# Sheet2.net
KiCad netlist of a schematic drawn in Altium Designer
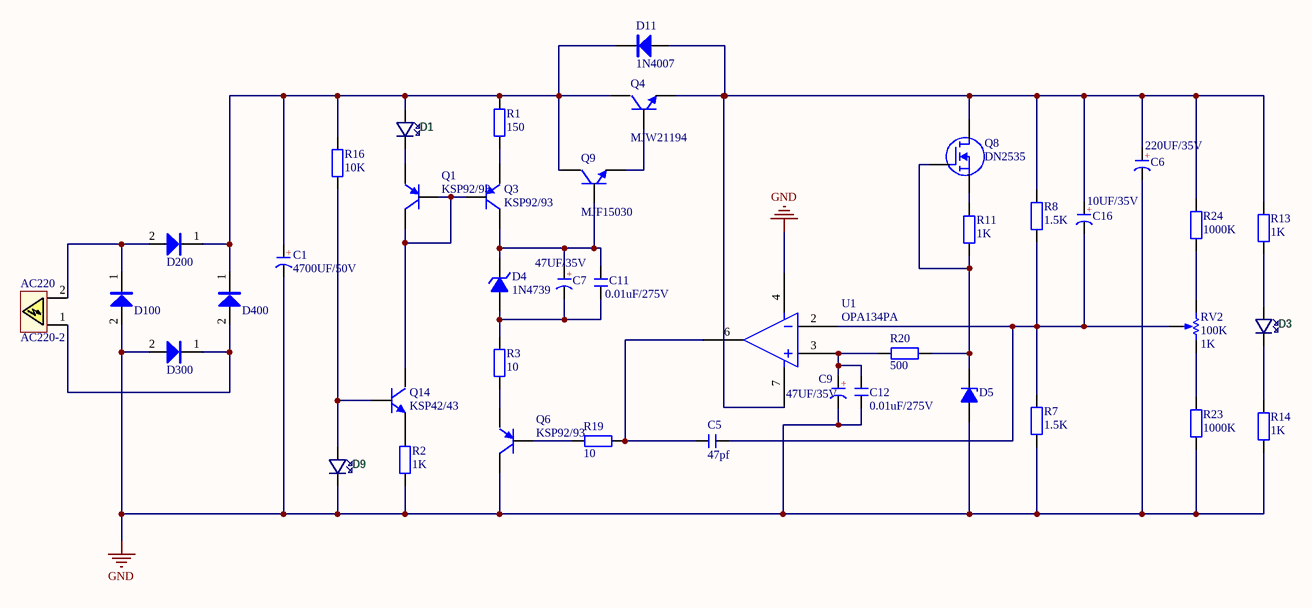
[diagram p0: Sheet2.SchDoc]

(export (version "E")
  (design (tool "Eeschema 10.0.6"))
  (components
    (comp (ref "AC220")
      (value "AC220-2")
      (footprint "HX5.08-2L")
      (libsource (lib "Connectors") (part "AC220-2"))
    )
    (comp (ref "C1")
      (value "4700UF/50V")
      (footprint "CAP 10*22*40")
      (description "直插电解电容")
      (fields (field (name "版权归属") "源创客"))
      (libsource (lib "电阻-电容-电感") (part "C-CAP"))
    )
    (comp (ref "C5")
      (value "47pf")
      (footprint "CC 2.2*5")
      (description "直插瓷片电容")
      (fields (field (name "版权归属") "源创客"))
      (libsource (lib "电阻-电容-电感") (part "C-CC"))
    )
    (comp (ref "C6")
      (value "220UF/35V")
      (footprint "CAP 5.0*10*20")
      (description "直插电解电容")
      (libsource (lib "电阻-电容-电感") (part "C-CAP"))
    )
    (comp (ref "C7")
      (value "47UF/35V")
      (footprint "CAP 5.0*10*20")
      (description "直插电解电容")
      (libsource (lib "电阻-电容-电感") (part "C-CAP"))
    )
    (comp (ref "C9")
      (value "47UF/35V")
      (footprint "CAP 5.0*10*20")
      (description "直插电解电容")
      (fields (field (name "版权归属") "源创客"))
      (libsource (lib "电阻-电容-电感") (part "C-CAP"))
    )
    (comp (ref "C11")
      (value "0.01uF/275V")
      (footprint "CBB 6.3*6.3*5")
      (description "CBB电容")
      (fields (field (name "版权归属") "源创客"))
      (libsource (lib "电阻-电容-电感") (part "C-CBB"))
    )
    (comp (ref "C12")
      (value "0.01uF/275V")
      (footprint "CBB 6.3*6.3*5")
      (description "CBB电容")
      (fields (field (name "版权归属") "源创客"))
      (libsource (lib "电阻-电容-电感") (part "C-CBB"))
    )
    (comp (ref "C16")
      (value "10UF/35V")
      (footprint "CAP 5.0*10*20")
      (description "直插电解电容")
      (libsource (lib "电阻-电容-电感") (part "C-CAP"))
    )
    (comp (ref "D1")
      (value "~")
      (footprint "LED 3MM-R")
      (description "直插式LED")
      (libsource (lib "LED") (part "LED"))
    )
    (comp (ref "D3")
      (value "~")
      (footprint "LED 3MM-R")
      (description "直插式LED")
      (libsource (lib "LED") (part "LED"))
    )
    (comp (ref "D4")
      (value "1N4739")
      (footprint "DO-41")
      (description "9.1V/1W稳压管")
      (libsource (lib "二极管-整流桥") (part "1N4739"))
    )
    (comp (ref "D5")
      (value "LT1021-10-2P")
      (footprint "DIP8-300_MH")
      (description "10V Precision Reference 2 Pin Config")
      (libsource (lib "电压参考") (part "LT1021-10-2P"))
    )
    (comp (ref "D9")
      (value "~")
      (footprint "LED 3MM-R")
      (description "直插式LED")
      (libsource (lib "LED") (part "LED"))
    )
    (comp (ref "D11")
      (value "1N4007")
      (footprint "DO-41")
      (description "整流二极管")
      (libsource (lib "二极管-整流桥") (part "1N4007"))
    )
    (comp (ref "D100")
      (value "VS-HFA08TB60-M3")
      (footprint "TO220AC")
      (description "Ultrafast Soft Recovery Diado 8A 600V")
      (libsource (lib "二极管-整流桥") (part "VS-HFA08TB60-M3"))
    )
    (comp (ref "D200")
      (value "VS-HFA08TB60-M3")
      (footprint "TO220AC")
      (description "Ultrafast Soft Recovery Diado 8A 600V")
      (libsource (lib "二极管-整流桥") (part "VS-HFA08TB60-M3"))
    )
    (comp (ref "D300")
      (value "VS-HFA08TB60-M3")
      (footprint "TO220AC")
      (description "Ultrafast Soft Recovery Diado 8A 600V")
      (libsource (lib "二极管-整流桥") (part "VS-HFA08TB60-M3"))
    )
    (comp (ref "D400")
      (value "VS-HFA08TB60-M3")
      (footprint "TO220AC")
      (description "Ultrafast Soft Recovery Diado 8A 600V")
      (libsource (lib "二极管-整流桥") (part "VS-HFA08TB60-M3"))
    )
    (comp (ref "Q1")
      (value "KSP92/93")
      (footprint "TO92A")
      (description "High Voltage PNP Transistor")
      (libsource (lib "三极管") (part "KSP92/93"))
    )
    (comp (ref "Q3")
      (value "KSP92/93")
      (footprint "TO92A")
      (description "High Voltage PNP Transistor")
      (libsource (lib "三极管") (part "KSP92/93"))
    )
    (comp (ref "Q4")
      (value "MJW21194")
      (footprint "TO247V")
      (description "Power NPN Transistor")
      (libsource (lib "三极管") (part "MJW21194"))
    )
    (comp (ref "Q6")
      (value "KSP92/93")
      (footprint "TO92A")
      (description "High Voltage PNP Transistor")
      (libsource (lib "三极管") (part "KSP92/93"))
    )
    (comp (ref "Q8")
      (value "DN2535")
      (footprint "TO92A")
      (description "N沟道耗尽型DMOS场效应管")
      (libsource (lib "场效应管") (part "DN2535"))
    )
    (comp (ref "Q9")
      (value "MJF15030")
      (footprint "TO220V")
      (description "Power NPN Transistor")
      (libsource (lib "三极管") (part "MJF15030"))
    )
    (comp (ref "Q14")
      (value "KSP42/43")
      (footprint "TO92A")
      (description "High Voltage NPN Transistor")
      (libsource (lib "三极管") (part "KSP42/43"))
    )
    (comp (ref "R1")
      (value "150")
      (footprint "RS 1/4W")
      (description "直插色环电阻")
      (libsource (lib "电阻-电容-电感") (part "R-CRR"))
    )
    (comp (ref "R2")
      (value "1K")
      (footprint "RS 1/4W")
      (description "直插色环电阻")
      (libsource (lib "电阻-电容-电感") (part "R-CRR"))
    )
    (comp (ref "R3")
      (value "10")
      (footprint "RS 1/4W")
      (description "直插色环电阻")
      (libsource (lib "电阻-电容-电感") (part "R-CRR"))
    )
    (comp (ref "R7")
      (value "1.5K")
      (footprint "RS 1/4W")
      (description "直插色环电阻")
      (libsource (lib "电阻-电容-电感") (part "R-CRR"))
    )
    (comp (ref "R8")
      (value "1.5K")
      (footprint "RS 1/4W")
      (description "直插色环电阻")
      (libsource (lib "电阻-电容-电感") (part "R-CRR"))
    )
    (comp (ref "R11")
      (value "1K")
      (footprint "RS 1/4W")
      (description "直插色环电阻")
      (libsource (lib "电阻-电容-电感") (part "R-CRR"))
    )
    (comp (ref "R13")
      (value "1K")
      (footprint "RS 1/4W")
      (description "直插色环电阻")
      (libsource (lib "电阻-电容-电感") (part "R-CRR"))
    )
    (comp (ref "R14")
      (value "1K")
      (footprint "RS 1/4W")
      (description "直插色环电阻")
      (fields (field (name "版权归属") "源创客"))
      (libsource (lib "电阻-电容-电感") (part "R-CRR"))
    )
    (comp (ref "R16")
      (value "10K")
      (footprint "RS 1/4W")
      (description "直插色环电阻")
      (fields (field (name "版权归属") "源创客"))
      (libsource (lib "电阻-电容-电感") (part "R-CRR"))
    )
    (comp (ref "R19")
      (value "10")
      (footprint "RS 1/4W")
      (description "直插色环电阻")
      (libsource (lib "电阻-电容-电感") (part "R-CRR"))
    )
    (comp (ref "R20")
      (value "500")
      (footprint "RS 1/4W")
      (description "直插色环电阻")
      (libsource (lib "电阻-电容-电感") (part "R-CRR"))
    )
    (comp (ref "R23")
      (value "1000K")
      (footprint "RS 1/4W")
      (description "直插色环电阻")
      (libsource (lib "电阻-电容-电感") (part "R-CRR"))
    )
    (comp (ref "R24")
      (value "1000K")
      (footprint "RS 1/4W")
      (description "直插色环电阻")
      (libsource (lib "电阻-电容-电感") (part "R-CRR"))
    )
    (comp (ref "RV2")
      (value "100K")
      (footprint "VR5")
      (description "Potentiometer")
      (fields (field (name "ALTIUM_VALUE") "1K") (field (name "PUBLISHER") "Altium Limited"))
      (libsource (lib "Miscellaneous Devices") (part "RPot"))
    )
    (comp (ref "U1") (value "OPA134PA") (footprint "DIP8-300_MH") (libsource (lib "运放") (part "OPA134PA")))
  )
  (nets
    (net (code "1") (name "GND") (class "Default")
      (node (ref "C1") (pin "2") (pinfunction "K_2") (pintype "passive"))
      (node (ref "C12") (pin "2") (pinfunction "2_2") (pintype "passive"))
      (node (ref "C6") (pin "2") (pinfunction "K_2") (pintype "passive"))
      (node (ref "C9") (pin "2") (pinfunction "K_2") (pintype "passive"))
      (node (ref "D100") (pin "2") (pinfunction "Anode_2") (pintype "passive"))
      (node (ref "D300") (pin "2") (pinfunction "Anode_2") (pintype "passive"))
      (node (ref "D5") (pin "4") (pinfunction "A_4") (pintype "passive"))
      (node (ref "D9") (pin "K") (pintype "passive"))
      (node (ref "Q6") (pin "3") (pinfunction "C_3") (pintype "passive"))
      (node (ref "R14") (pin "1") (pinfunction "1_1") (pintype "passive"))
      (node (ref "R2") (pin "1") (pinfunction "1_1") (pintype "passive"))
      (node (ref "R23") (pin "1") (pinfunction "1_1") (pintype "passive"))
      (node (ref "R7") (pin "1") (pinfunction "1_1") (pintype "passive"))
      (node (ref "U1") (pin "4") (pinfunction "V-_4") (pintype "passive"))
    )
    (net (code "2") (name "Net-(AC220-G)") (class "Default")
      (node (ref "AC220") (pin "2") (pinfunction "G_2") (pintype "passive"))
      (node (ref "D100") (pin "1") (pinfunction "Cathode_1") (pintype "passive"))
      (node (ref "D200") (pin "2") (pinfunction "Anode_2") (pintype "passive"))
    )
    (net (code "3") (name "Net-(AC220-L)") (class "Default")
      (node (ref "AC220") (pin "1") (pinfunction "L_1") (pintype "passive"))
      (node (ref "D300") (pin "1") (pinfunction "Cathode_1") (pintype "passive"))
      (node (ref "D400") (pin "2") (pinfunction "Anode_2") (pintype "passive"))
    )
    (net (code "4") (name "Net-(C1-A)") (class "Default")
      (node (ref "C1") (pin "1") (pinfunction "A_1") (pintype "passive"))
      (node (ref "D1") (pin "A") (pintype "passive"))
      (node (ref "D11") (pin "2") (pinfunction "K_2") (pintype "passive"))
      (node (ref "D200") (pin "1") (pinfunction "Cathode_1") (pintype "passive"))
      (node (ref "D400") (pin "1") (pinfunction "Cathode_1") (pintype "passive"))
      (node (ref "Q4") (pin "2") (pinfunction "C_2") (pintype "passive"))
      (node (ref "Q9") (pin "2") (pinfunction "C_2") (pintype "passive"))
      (node (ref "R1") (pin "2") (pinfunction "2_2") (pintype "passive"))
      (node (ref "R16") (pin "2") (pinfunction "2_2") (pintype "passive"))
    )
    (net (code "5") (name "Net-(C7-A)") (class "Default")
      (node (ref "C11") (pin "1") (pinfunction "1_1") (pintype "passive"))
      (node (ref "C7") (pin "1") (pinfunction "A_1") (pintype "passive"))
      (node (ref "D4") (pin "2") (pinfunction "K_2") (pintype "passive"))
      (node (ref "Q3") (pin "3") (pinfunction "C_3") (pintype "passive"))
      (node (ref "Q9") (pin "1") (pinfunction "B_1") (pintype "passive"))
    )
    (net (code "6") (name "Net-(C7-K)") (class "Default")
      (node (ref "C11") (pin "2") (pinfunction "2_2") (pintype "passive"))
      (node (ref "C7") (pin "2") (pinfunction "K_2") (pintype "passive"))
      (node (ref "D4") (pin "1") (pinfunction "A_1") (pintype "passive"))
      (node (ref "R3") (pin "2") (pinfunction "2_2") (pintype "passive"))
    )
    (net (code "7") (name "Net-(C9-A)") (class "Default")
      (node (ref "C12") (pin "1") (pinfunction "1_1") (pintype "passive"))
      (node (ref "C9") (pin "1") (pinfunction "A_1") (pintype "passive"))
      (node (ref "R20") (pin "2") (pinfunction "2_2") (pintype "passive"))
      (node (ref "U1") (pin "3") (pinfunction "+in_3") (pintype "passive"))
    )
    (net (code "8") (name "Net-(C16-A)") (class "Default")
      (node (ref "C16") (pin "1") (pinfunction "A_1") (pintype "passive"))
      (node (ref "C6") (pin "1") (pinfunction "A_1") (pintype "passive"))
      (node (ref "D11") (pin "1") (pinfunction "A_1") (pintype "passive"))
      (node (ref "Q4") (pin "3") (pinfunction "E_3") (pintype "passive"))
      (node (ref "Q8") (pin "3") (pinfunction "D_3") (pintype "passive"))
      (node (ref "R13") (pin "2") (pinfunction "2_2") (pintype "passive"))
      (node (ref "R24") (pin "2") (pinfunction "2_2") (pintype "passive"))
      (node (ref "R8") (pin "2") (pinfunction "2_2") (pintype "passive"))
      (node (ref "U1") (pin "7") (pinfunction "V+_7") (pintype "passive"))
    )
    (net (code "9") (name "Net-(C16-K)") (class "Default")
      (node (ref "C16") (pin "2") (pinfunction "K_2") (pintype "passive"))
      (node (ref "C5") (pin "2") (pinfunction "2_2") (pintype "passive"))
      (node (ref "R7") (pin "2") (pinfunction "2_2") (pintype "passive"))
      (node (ref "R8") (pin "1") (pinfunction "1_1") (pintype "passive"))
      (node (ref "RV2") (pin "3") (pinfunction "TAP_3") (pintype "passive"))
      (node (ref "U1") (pin "2") (pinfunction "-in_2") (pintype "passive"))
    )
    (net (code "10") (name "Net-(D3-PadA)") (class "Default")
      (node (ref "D3") (pin "A") (pintype "passive"))
      (node (ref "R13") (pin "1") (pinfunction "1_1") (pintype "passive"))
    )
    (net (code "11") (name "Net-(D3-PadK)") (class "Default")
      (node (ref "D3") (pin "K") (pintype "passive"))
      (node (ref "R14") (pin "2") (pinfunction "2_2") (pintype "passive"))
    )
    (net (code "12") (name "Net-(D5-K)") (class "Default")
      (node (ref "D5") (pin "6") (pinfunction "K_6") (pintype "passive"))
      (node (ref "Q8") (pin "2") (pinfunction "G_2") (pintype "passive"))
      (node (ref "R11") (pin "1") (pinfunction "1_1") (pintype "passive"))
      (node (ref "R20") (pin "1") (pinfunction "1_1") (pintype "passive"))
    )
    (net (code "13") (name "Net-(Q1-B)") (class "Default")
      (node (ref "Q1") (pin "2") (pinfunction "B_2") (pintype "passive"))
      (node (ref "Q1") (pin "3") (pinfunction "C_3") (pintype "passive"))
      (node (ref "Q14") (pin "3") (pinfunction "C_3") (pintype "passive"))
      (node (ref "Q3") (pin "2") (pinfunction "B_2") (pintype "passive"))
    )
    (net (code "14") (name "Net-(Q1-E)") (class "Default")
      (node (ref "D1") (pin "K") (pintype "passive"))
      (node (ref "Q1") (pin "1") (pinfunction "E_1") (pintype "passive"))
    )
    (net (code "15") (name "Net-(Q3-E)") (class "Default")
      (node (ref "Q3") (pin "1") (pinfunction "E_1") (pintype "passive"))
      (node (ref "R1") (pin "1") (pinfunction "1_1") (pintype "passive"))
    )
    (net (code "16") (name "Net-(Q4-B)") (class "Default")
      (node (ref "Q4") (pin "1") (pinfunction "B_1") (pintype "passive"))
      (node (ref "Q9") (pin "3") (pinfunction "E_3") (pintype "passive"))
    )
    (net (code "17") (name "Net-(Q6-B)") (class "Default")
      (node (ref "Q6") (pin "2") (pinfunction "B_2") (pintype "passive"))
      (node (ref "R19") (pin "2") (pinfunction "2_2") (pintype "passive"))
    )
    (net (code "18") (name "Net-(Q6-E)") (class "Default")
      (node (ref "Q6") (pin "1") (pinfunction "E_1") (pintype "passive"))
      (node (ref "R3") (pin "1") (pinfunction "1_1") (pintype "passive"))
    )
    (net (code "19") (name "Net-(Q8-S)") (class "Default")
      (node (ref "Q8") (pin "1") (pinfunction "S_1") (pintype "passive"))
      (node (ref "R11") (pin "2") (pinfunction "2_2") (pintype "passive"))
    )
    (net (code "20") (name "Net-(Q14-B)") (class "Default")
      (node (ref "D9") (pin "A") (pintype "passive"))
      (node (ref "Q14") (pin "2") (pinfunction "B_2") (pintype "passive"))
      (node (ref "R16") (pin "1") (pinfunction "1_1") (pintype "passive"))
    )
    (net (code "21") (name "Net-(Q14-E)") (class "Default")
      (node (ref "Q14") (pin "1") (pinfunction "E_1") (pintype "passive"))
      (node (ref "R2") (pin "2") (pinfunction "2_2") (pintype "passive"))
    )
    (net (code "22") (name "Net-(RV2-BOT)") (class "Default")
      (node (ref "R23") (pin "2") (pinfunction "2_2") (pintype "passive"))
      (node (ref "RV2") (pin "2") (pinfunction "BOT_2") (pintype "passive"))
    )
    (net (code "23") (name "Net-(RV2-TOP)") (class "Default")
      (node (ref "R24") (pin "1") (pinfunction "1_1") (pintype "passive"))
      (node (ref "RV2") (pin "1") (pinfunction "TOP_1") (pintype "passive"))
    )
    (net (code "24") (name "Net-(U1-out)") (class "Default")
      (node (ref "C5") (pin "1") (pinfunction "1_1") (pintype "passive"))
      (node (ref "R19") (pin "1") (pinfunction "1_1") (pintype "passive"))
      (node (ref "U1") (pin "6") (pinfunction "out_6") (pintype "passive"))
    )
  )
)
